# core_power.net
KiCad netlist of a schematic drawn in Altium Designer
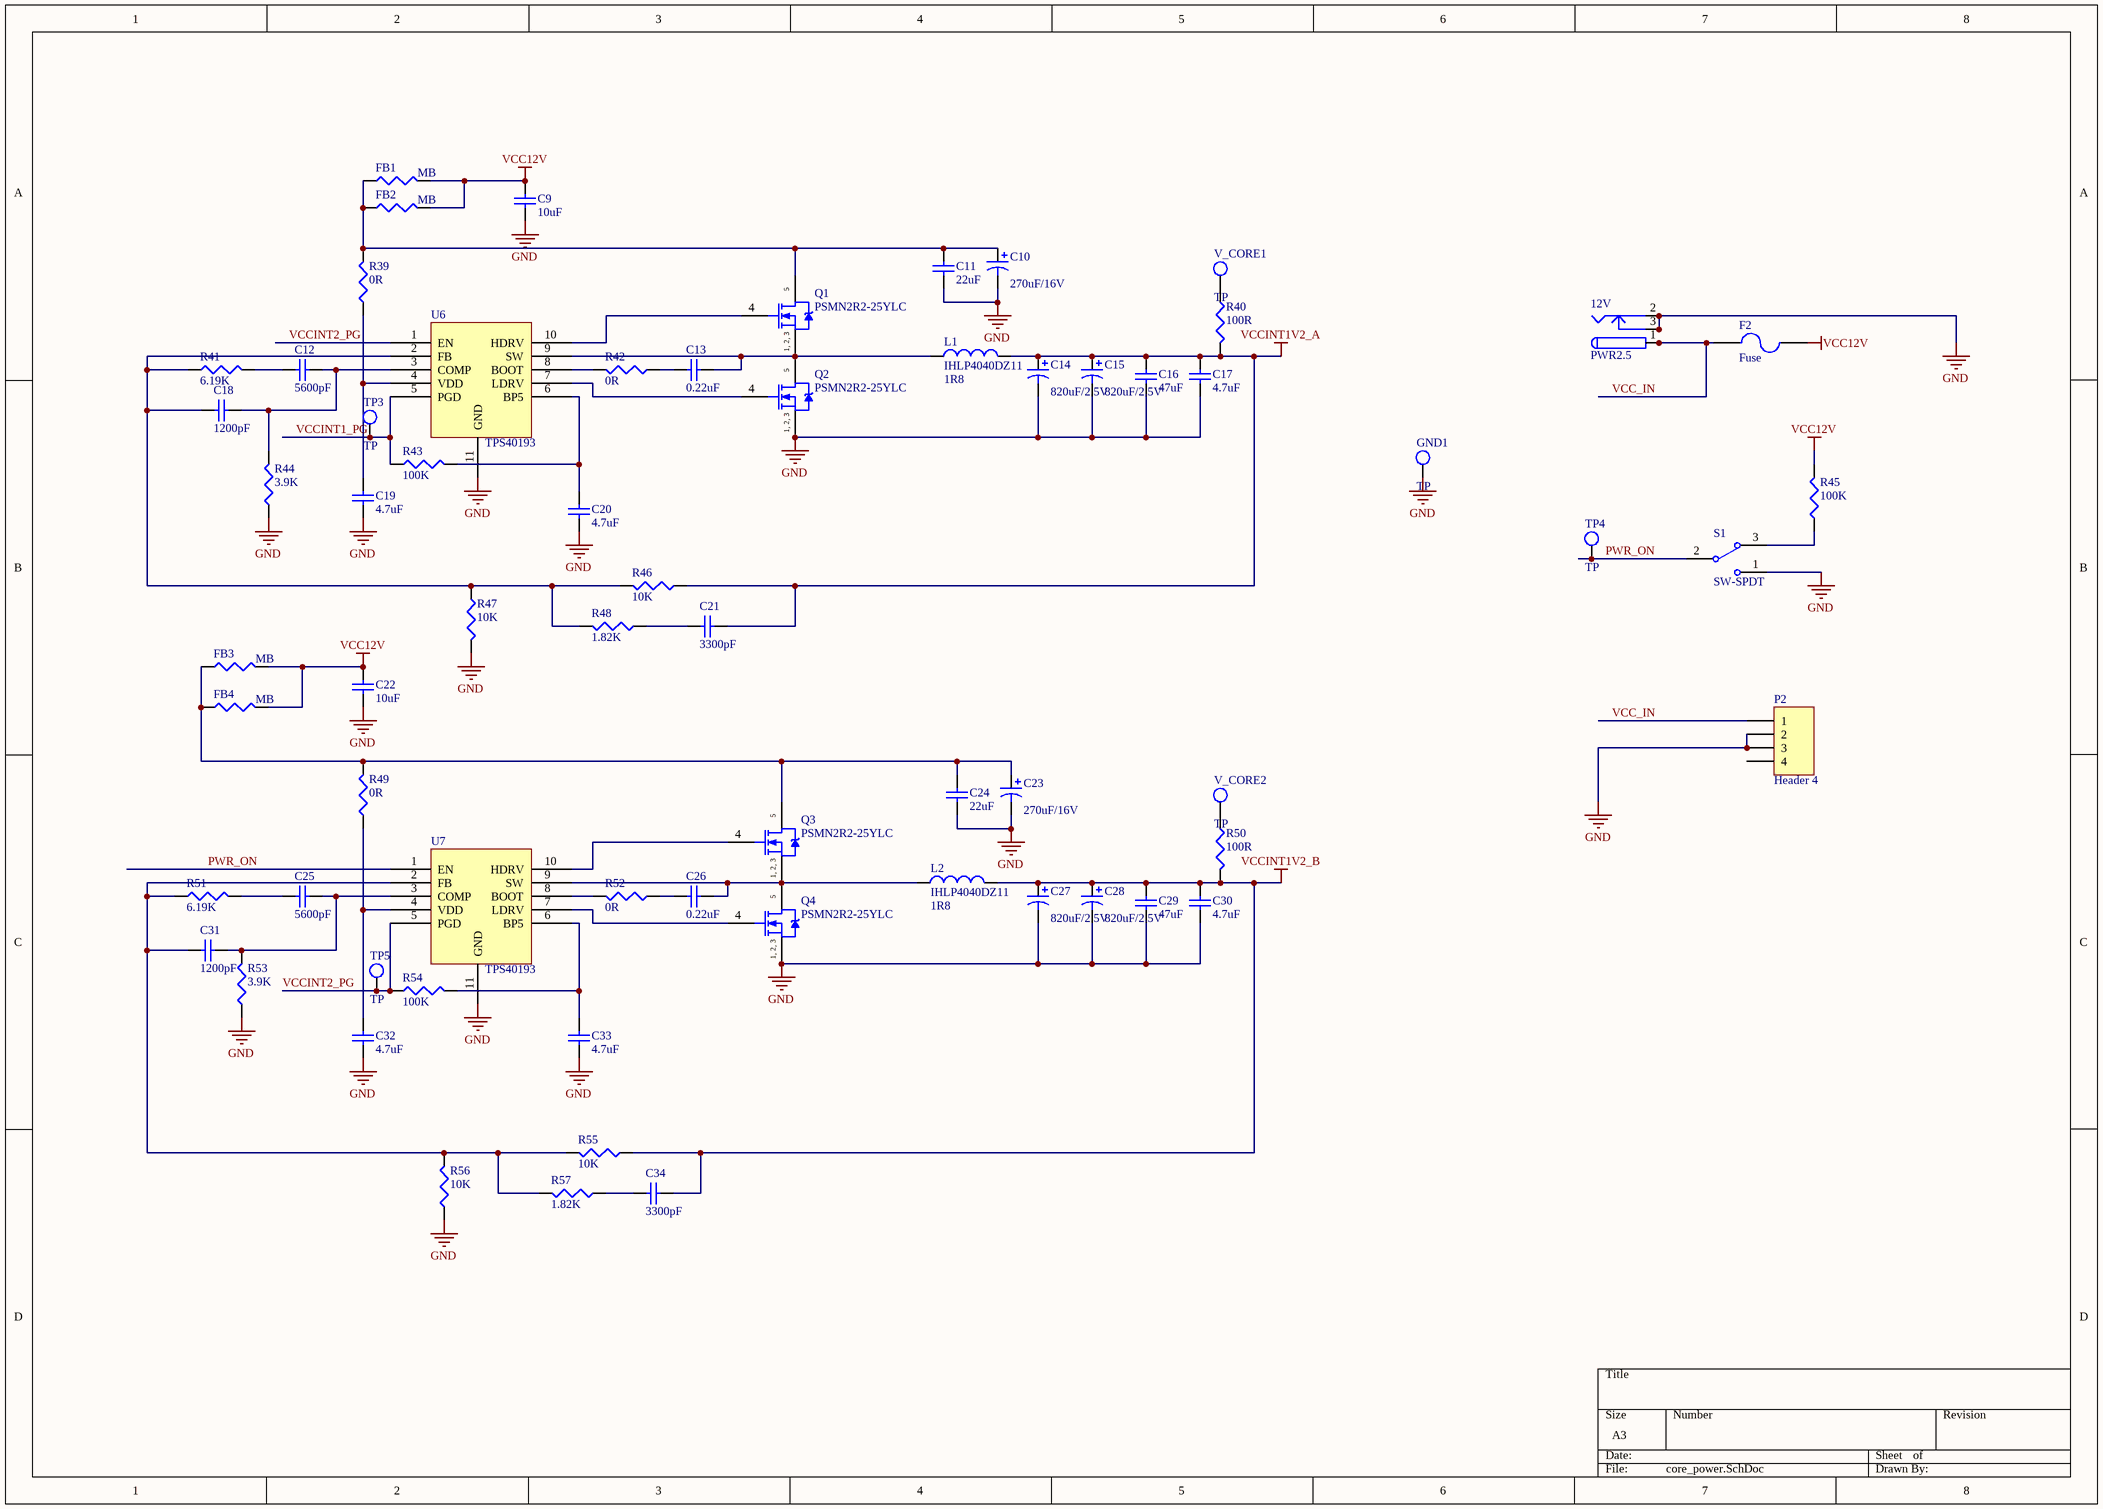
[diagram p0: core_power.SchDoc]

(export (version "E")
  (design (tool "Eeschema 10.0.6"))
  (components
    (comp (ref "12V")
      (value "PWR2.5")
      (footprint "KLD-0202")
      (description "Low Voltage Power Supply Connector")
      (fields (field (name "PUBLISHER") "Altium Limited"))
      (libsource (lib "Miscellaneous Connectors") (part "PWR2.5"))
    )
    (comp (ref "C9")
      (value "10uF")
      (footprint "CAPC3216N")
      (description "Capacitor (Semiconductor SIM Model)")
      (fields (field (name "PUBLISHER") "Altium Limited"))
      (libsource (lib "Miscellaneous Devices") (part "Cap Semi"))
    )
    (comp (ref "C10")
      (value "270uF/16V")
      (footprint "CAP8X8")
      (description "Polarized Capacitor (Radial)")
      (fields (field (name "PUBLISHER") "Altium Limited"))
      (libsource (lib "Miscellaneous Devices") (part "Cap Pol1"))
    )
    (comp (ref "C11")
      (value "22uF")
      (footprint "CAPC3225N")
      (description "Capacitor (Semiconductor SIM Model)")
      (fields (field (name "PUBLISHER") "Altium Limited"))
      (libsource (lib "Miscellaneous Devices") (part "Cap Semi"))
    )
    (comp (ref "C12")
      (value "5600pF")
      (footprint "CAPC1608N")
      (description "Capacitor (Semiconductor SIM Model)")
      (fields (field (name "PUBLISHER") "Altium Limited"))
      (libsource (lib "Miscellaneous Devices") (part "Cap Semi"))
    )
    (comp (ref "C13")
      (value "0.22uF")
      (footprint "CAPC1608N")
      (description "Capacitor (Semiconductor SIM Model)")
      (fields (field (name "PUBLISHER") "Altium Limited"))
      (libsource (lib "Miscellaneous Devices") (part "Cap Semi"))
    )
    (comp (ref "C14")
      (value "820uF/2.5V")
      (footprint "CAP8X8")
      (description "Polarized Capacitor (Radial)")
      (fields (field (name "PUBLISHER") "Altium Limited"))
      (libsource (lib "Miscellaneous Devices") (part "Cap Pol1"))
    )
    (comp (ref "C15")
      (value "820uF/2.5V")
      (footprint "CAP8X8")
      (description "Polarized Capacitor (Radial)")
      (fields (field (name "PUBLISHER") "Altium Limited"))
      (libsource (lib "Miscellaneous Devices") (part "Cap Pol1"))
    )
    (comp (ref "C16")
      (value "47uF")
      (footprint "CAPC3225N")
      (description "Capacitor (Semiconductor SIM Model)")
      (fields (field (name "PUBLISHER") "Altium Limited"))
      (libsource (lib "Miscellaneous Devices") (part "Cap Semi"))
    )
    (comp (ref "C17")
      (value "4.7uF")
      (footprint "CAPC1608N")
      (description "Capacitor (Semiconductor SIM Model)")
      (fields (field (name "PUBLISHER") "Altium Limited"))
      (libsource (lib "Miscellaneous Devices") (part "Cap Semi"))
    )
    (comp (ref "C18")
      (value "1200pF")
      (footprint "CAPC1608N")
      (description "Capacitor (Semiconductor SIM Model)")
      (fields (field (name "PUBLISHER") "Altium Limited"))
      (libsource (lib "Miscellaneous Devices") (part "Cap Semi"))
    )
    (comp (ref "C19")
      (value "4.7uF")
      (footprint "CAPC2012N")
      (description "Capacitor (Semiconductor SIM Model)")
      (fields (field (name "PUBLISHER") "Altium Limited"))
      (libsource (lib "Miscellaneous Devices") (part "Cap Semi"))
    )
    (comp (ref "C20")
      (value "4.7uF")
      (footprint "CAPC2012N")
      (description "Capacitor (Semiconductor SIM Model)")
      (fields (field (name "PUBLISHER") "Altium Limited"))
      (libsource (lib "Miscellaneous Devices") (part "Cap Semi"))
    )
    (comp (ref "C21")
      (value "3300pF")
      (footprint "CAPC1608N")
      (description "Capacitor (Semiconductor SIM Model)")
      (fields (field (name "PUBLISHER") "Altium Limited"))
      (libsource (lib "Miscellaneous Devices") (part "Cap Semi"))
    )
    (comp (ref "C22")
      (value "10uF")
      (footprint "CAPC3216N")
      (description "Capacitor (Semiconductor SIM Model)")
      (fields (field (name "PUBLISHER") "Altium Limited"))
      (libsource (lib "Miscellaneous Devices") (part "Cap Semi"))
    )
    (comp (ref "C23")
      (value "270uF/16V")
      (footprint "CAP8X8")
      (description "Polarized Capacitor (Radial)")
      (fields (field (name "PUBLISHER") "Altium Limited"))
      (libsource (lib "Miscellaneous Devices") (part "Cap Pol1"))
    )
    (comp (ref "C24")
      (value "22uF")
      (footprint "CAPC3225N")
      (description "Capacitor (Semiconductor SIM Model)")
      (fields (field (name "PUBLISHER") "Altium Limited"))
      (libsource (lib "Miscellaneous Devices") (part "Cap Semi"))
    )
    (comp (ref "C25")
      (value "5600pF")
      (footprint "CAPC1608N")
      (description "Capacitor (Semiconductor SIM Model)")
      (fields (field (name "PUBLISHER") "Altium Limited"))
      (libsource (lib "Miscellaneous Devices") (part "Cap Semi"))
    )
    (comp (ref "C26")
      (value "0.22uF")
      (footprint "CAPC1608N")
      (description "Capacitor (Semiconductor SIM Model)")
      (fields (field (name "PUBLISHER") "Altium Limited"))
      (libsource (lib "Miscellaneous Devices") (part "Cap Semi"))
    )
    (comp (ref "C27")
      (value "820uF/2.5V")
      (footprint "CAP8X8")
      (description "Polarized Capacitor (Radial)")
      (fields (field (name "PUBLISHER") "Altium Limited"))
      (libsource (lib "Miscellaneous Devices") (part "Cap Pol1"))
    )
    (comp (ref "C28")
      (value "820uF/2.5V")
      (footprint "CAP8X8")
      (description "Polarized Capacitor (Radial)")
      (fields (field (name "PUBLISHER") "Altium Limited"))
      (libsource (lib "Miscellaneous Devices") (part "Cap Pol1"))
    )
    (comp (ref "C29")
      (value "47uF")
      (footprint "CAPC3225N")
      (description "Capacitor (Semiconductor SIM Model)")
      (fields (field (name "PUBLISHER") "Altium Limited"))
      (libsource (lib "Miscellaneous Devices") (part "Cap Semi"))
    )
    (comp (ref "C30")
      (value "4.7uF")
      (footprint "CAPC1608N")
      (description "Capacitor (Semiconductor SIM Model)")
      (fields (field (name "PUBLISHER") "Altium Limited"))
      (libsource (lib "Miscellaneous Devices") (part "Cap Semi"))
    )
    (comp (ref "C31")
      (value "1200pF")
      (footprint "CAPC1608N")
      (description "Capacitor (Semiconductor SIM Model)")
      (fields (field (name "PUBLISHER") "Altium Limited"))
      (libsource (lib "Miscellaneous Devices") (part "Cap Semi"))
    )
    (comp (ref "C32")
      (value "4.7uF")
      (footprint "CAPC2012N")
      (description "Capacitor (Semiconductor SIM Model)")
      (fields (field (name "PUBLISHER") "Altium Limited"))
      (libsource (lib "Miscellaneous Devices") (part "Cap Semi"))
    )
    (comp (ref "C33")
      (value "4.7uF")
      (footprint "CAPC2012N")
      (description "Capacitor (Semiconductor SIM Model)")
      (fields (field (name "PUBLISHER") "Altium Limited"))
      (libsource (lib "Miscellaneous Devices") (part "Cap Semi"))
    )
    (comp (ref "C34")
      (value "3300pF")
      (footprint "CAPC1608N")
      (description "Capacitor (Semiconductor SIM Model)")
      (fields (field (name "PUBLISHER") "Altium Limited"))
      (libsource (lib "Miscellaneous Devices") (part "Cap Semi"))
    )
    (comp (ref "F2")
      (value "Fuse")
      (footprint "RESC5025N")
      (fields (field (name "PUBLISHER") "Altium Limited"))
      (libsource (lib "Miscellaneous Devices") (part "Fuse 2"))
    )
    (comp (ref "FB1")
      (value "MB")
      (footprint "INDC3216N")
      (description "Resistor")
      (fields (field (name "PUBLISHER") "Altium Limited"))
      (libsource (lib "Miscellaneous Devices") (part "Res3"))
    )
    (comp (ref "FB2")
      (value "MB")
      (footprint "INDC3216N")
      (description "Resistor")
      (fields (field (name "PUBLISHER") "Altium Limited"))
      (libsource (lib "Miscellaneous Devices") (part "Res3"))
    )
    (comp (ref "FB3")
      (value "MB")
      (footprint "INDC3216N")
      (description "Resistor")
      (fields (field (name "PUBLISHER") "Altium Limited"))
      (libsource (lib "Miscellaneous Devices") (part "Res3"))
    )
    (comp (ref "FB4")
      (value "MB")
      (footprint "INDC3216N")
      (description "Resistor")
      (fields (field (name "PUBLISHER") "Altium Limited"))
      (libsource (lib "Miscellaneous Devices") (part "Res3"))
    )
    (comp (ref "GND1") (value "TP") (footprint "PIN1") (libsource (lib "S6") (part "TP")))
    (comp (ref "L1")
      (value "IHLP4040DZ11")
      (footprint "IHLP4040")
      (description "Inductor")
      (fields (field (name "ALTIUM_VALUE") "1R8") (field (name "PUBLISHER") "Altium Limited"))
      (libsource (lib "Miscellaneous Devices") (part "Inductor"))
    )
    (comp (ref "L2")
      (value "IHLP4040DZ11")
      (footprint "IHLP4040")
      (description "Inductor")
      (fields (field (name "ALTIUM_VALUE") "1R8") (field (name "PUBLISHER") "Altium Limited"))
      (libsource (lib "Miscellaneous Devices") (part "Inductor"))
    )
    (comp (ref "P2")
      (value "Header 4")
      (footprint "S61:015244441")
      (description "Header, 4-Pin")
      (fields (field (name "PUBLISHER") "Altium Limited"))
      (libsource (lib "Miscellaneous Connectors") (part "Header 4"))
    )
    (comp (ref "Q1") (value "PSMN2R2-25YLC") (footprint "LFPAK") (libsource (lib "S6") (part "HAT216X")))
    (comp (ref "Q2") (value "PSMN2R2-25YLC") (footprint "LFPAK") (libsource (lib "S6") (part "HAT216X")))
    (comp (ref "Q3") (value "PSMN2R2-25YLC") (footprint "LFPAK") (libsource (lib "S6") (part "HAT216X")))
    (comp (ref "Q4") (value "PSMN2R2-25YLC") (footprint "LFPAK") (libsource (lib "S6") (part "HAT216X")))
    (comp (ref "R39")
      (value "0R")
      (footprint "RESC1608N")
      (description "Resistor")
      (fields (field (name "PUBLISHER") "Altium Limited"))
      (libsource (lib "Miscellaneous Devices") (part "Res3"))
    )
    (comp (ref "R40")
      (value "100R")
      (footprint "RESC1005N")
      (description "Resistor")
      (fields (field (name "PUBLISHER") "Altium Limited"))
      (libsource (lib "Miscellaneous Devices") (part "Res3"))
    )
    (comp (ref "R41")
      (value "6.19K")
      (footprint "RESC1608N")
      (description "Resistor")
      (fields (field (name "PUBLISHER") "Altium Limited"))
      (libsource (lib "Miscellaneous Devices") (part "Res3"))
    )
    (comp (ref "R42")
      (value "0R")
      (footprint "RESC1608N")
      (description "Resistor")
      (fields (field (name "PUBLISHER") "Altium Limited"))
      (libsource (lib "Miscellaneous Devices") (part "Res3"))
    )
    (comp (ref "R43")
      (value "100K")
      (footprint "RESC1005N")
      (description "Resistor")
      (fields (field (name "PUBLISHER") "Altium Limited"))
      (libsource (lib "Miscellaneous Devices") (part "Res3"))
    )
    (comp (ref "R44")
      (value "3.9K")
      (footprint "RESC1608N")
      (description "Resistor")
      (fields (field (name "PUBLISHER") "Altium Limited"))
      (libsource (lib "Miscellaneous Devices") (part "Res3"))
    )
    (comp (ref "R45")
      (value "100K")
      (footprint "RESC1005N")
      (description "Resistor")
      (fields (field (name "PUBLISHER") "Altium Limited"))
      (libsource (lib "Miscellaneous Devices") (part "Res3"))
    )
    (comp (ref "R46")
      (value "10K")
      (footprint "RESC1608N")
      (description "Resistor")
      (fields (field (name "PUBLISHER") "Altium Limited"))
      (libsource (lib "Miscellaneous Devices") (part "Res3"))
    )
    (comp (ref "R47")
      (value "10K")
      (footprint "RESC1608N")
      (description "Resistor")
      (fields (field (name "PUBLISHER") "Altium Limited"))
      (libsource (lib "Miscellaneous Devices") (part "Res3"))
    )
    (comp (ref "R48")
      (value "1.82K")
      (footprint "RESC1608N")
      (description "Resistor")
      (fields (field (name "PUBLISHER") "Altium Limited"))
      (libsource (lib "Miscellaneous Devices") (part "Res3"))
    )
    (comp (ref "R49")
      (value "0R")
      (footprint "RESC1608N")
      (description "Resistor")
      (fields (field (name "PUBLISHER") "Altium Limited"))
      (libsource (lib "Miscellaneous Devices") (part "Res3"))
    )
    (comp (ref "R50")
      (value "100R")
      (footprint "RESC1005N")
      (description "Resistor")
      (fields (field (name "PUBLISHER") "Altium Limited"))
      (libsource (lib "Miscellaneous Devices") (part "Res3"))
    )
    (comp (ref "R51")
      (value "6.19K")
      (footprint "RESC1608N")
      (description "Resistor")
      (fields (field (name "PUBLISHER") "Altium Limited"))
      (libsource (lib "Miscellaneous Devices") (part "Res3"))
    )
    (comp (ref "R52")
      (value "0R")
      (footprint "RESC1608N")
      (description "Resistor")
      (fields (field (name "PUBLISHER") "Altium Limited"))
      (libsource (lib "Miscellaneous Devices") (part "Res3"))
    )
    (comp (ref "R53")
      (value "3.9K")
      (footprint "RESC1608N")
      (description "Resistor")
      (fields (field (name "PUBLISHER") "Altium Limited"))
      (libsource (lib "Miscellaneous Devices") (part "Res3"))
    )
    (comp (ref "R54")
      (value "100K")
      (footprint "RESC1005N")
      (description "Resistor")
      (fields (field (name "PUBLISHER") "Altium Limited"))
      (libsource (lib "Miscellaneous Devices") (part "Res3"))
    )
    (comp (ref "R55")
      (value "10K")
      (footprint "RESC1608N")
      (description "Resistor")
      (fields (field (name "PUBLISHER") "Altium Limited"))
      (libsource (lib "Miscellaneous Devices") (part "Res3"))
    )
    (comp (ref "R56")
      (value "10K")
      (footprint "RESC1608N")
      (description "Resistor")
      (fields (field (name "PUBLISHER") "Altium Limited"))
      (libsource (lib "Miscellaneous Devices") (part "Res3"))
    )
    (comp (ref "R57")
      (value "1.82K")
      (footprint "RESC1608N")
      (description "Resistor")
      (fields (field (name "PUBLISHER") "Altium Limited"))
      (libsource (lib "Miscellaneous Devices") (part "Res3"))
    )
    (comp (ref "S1")
      (value "SW-SPDT")
      (footprint "SW3_S")
      (description "SPDT Subminiature Toggle Switch, Right Angle Mounting, Vertical Actuation")
      (fields (field (name "PUBLISHER") "Altium Limited"))
      (libsource (lib "Miscellaneous Devices") (part "SW-SPDT"))
    )
    (comp (ref "TP3") (value "TP") (footprint "TP") (libsource (lib "S6") (part "TP")))
    (comp (ref "TP4") (value "TP") (footprint "TP") (libsource (lib "S6") (part "TP")))
    (comp (ref "TP5") (value "TP") (footprint "TP") (libsource (lib "S6") (part "TP")))
    (comp (ref "U6") (value "TPS40193") (footprint "SON10") (libsource (lib "S6") (part "TPS40193")))
    (comp (ref "U7") (value "TPS40193") (footprint "SON10") (libsource (lib "S6") (part "TPS40193")))
    (comp (ref "V_CORE1") (value "TP") (footprint "PIN1") (libsource (lib "S6") (part "TP")))
    (comp (ref "V_CORE2") (value "TP") (footprint "PIN1") (libsource (lib "S6") (part "TP")))
  )
  (nets
    (net (code "1") (name "/PWR_ON") (class "Default")
      (node (ref "S1") (pin "2") (pinfunction "2_2") (pintype "passive"))
      (node (ref "TP4") (pin "1") (pinfunction "TP_1") (pintype "passive"))
      (node (ref "U7") (pin "1") (pinfunction "EN_1") (pintype "passive"))
    )
    (net (code "2") (name "/VCCINT1_PG") (class "Default")
      (node (ref "R43") (pin "1") (pinfunction "1_1") (pintype "passive"))
      (node (ref "TP3") (pin "1") (pinfunction "TP_1") (pintype "passive"))
      (node (ref "U6") (pin "5") (pinfunction "PGD_5") (pintype "passive"))
    )
    (net (code "3") (name "/VCCINT2_PG") (class "Default")
      (node (ref "R54") (pin "1") (pinfunction "1_1") (pintype "passive"))
      (node (ref "TP5") (pin "1") (pinfunction "TP_1") (pintype "passive"))
      (node (ref "U6") (pin "1") (pinfunction "EN_1") (pintype "passive"))
      (node (ref "U7") (pin "5") (pinfunction "PGD_5") (pintype "passive"))
    )
    (net (code "4") (name "/VCC_IN") (class "Default")
      (node (ref "12V") (pin "1") (pinfunction "1_1") (pintype "power_in"))
      (node (ref "12V") (pin "1A") (pinfunction "1A_1A") (pintype "power_in"))
      (node (ref "12V") (pin "1B") (pinfunction "1B_1B") (pintype "power_in"))
      (node (ref "F2") (pin "1") (pinfunction "1_1") (pintype "passive"))
      (node (ref "P2") (pin "1") (pinfunction "1_1") (pintype "passive"))
    )
    (net (code "5") (name "GND") (class "Default")
      (node (ref "12V") (pin "2") (pinfunction "2_2") (pintype "power_in"))
      (node (ref "12V") (pin "2A") (pinfunction "2A_2A") (pintype "power_in"))
      (node (ref "12V") (pin "2B") (pinfunction "2B_2B") (pintype "power_in"))
      (node (ref "12V") (pin "3") (pinfunction "3_3") (pintype "power_in"))
      (node (ref "12V") (pin "3A") (pinfunction "3A_3A") (pintype "power_in"))
      (node (ref "12V") (pin "3B") (pinfunction "3B_3B") (pintype "power_in"))
      (node (ref "C10") (pin "2") (pinfunction "2_2") (pintype "passive"))
      (node (ref "C11") (pin "1") (pinfunction "1_1") (pintype "passive"))
      (node (ref "C14") (pin "2") (pinfunction "2_2") (pintype "passive"))
      (node (ref "C15") (pin "2") (pinfunction "2_2") (pintype "passive"))
      (node (ref "C16") (pin "1") (pinfunction "1_1") (pintype "passive"))
      (node (ref "C17") (pin "1") (pinfunction "1_1") (pintype "passive"))
      (node (ref "C19") (pin "2") (pinfunction "2_2") (pintype "passive"))
      (node (ref "C20") (pin "1") (pinfunction "1_1") (pintype "passive"))
      (node (ref "C22") (pin "1") (pinfunction "1_1") (pintype "passive"))
      (node (ref "C23") (pin "2") (pinfunction "2_2") (pintype "passive"))
      (node (ref "C24") (pin "1") (pinfunction "1_1") (pintype "passive"))
      (node (ref "C27") (pin "2") (pinfunction "2_2") (pintype "passive"))
      (node (ref "C28") (pin "2") (pinfunction "2_2") (pintype "passive"))
      (node (ref "C29") (pin "1") (pinfunction "1_1") (pintype "passive"))
      (node (ref "C30") (pin "1") (pinfunction "1_1") (pintype "passive"))
      (node (ref "C32") (pin "1") (pinfunction "1_1") (pintype "passive"))
      (node (ref "C33") (pin "2") (pinfunction "2_2") (pintype "passive"))
      (node (ref "C9") (pin "1") (pinfunction "1_1") (pintype "passive"))
      (node (ref "GND1") (pin "1") (pinfunction "TP_1") (pintype "passive"))
      (node (ref "P2") (pin "2") (pinfunction "2_2") (pintype "passive"))
      (node (ref "P2") (pin "3") (pinfunction "3_3") (pintype "passive"))
      (node (ref "Q2") (pin "1") (pinfunction "S_1") (pintype "passive"))
      (node (ref "Q2") (pin "2") (pinfunction "S_2") (pintype "passive"))
      (node (ref "Q2") (pin "3") (pinfunction "S_3") (pintype "passive"))
      (node (ref "Q4") (pin "1") (pinfunction "S_1") (pintype "passive"))
      (node (ref "Q4") (pin "2") (pinfunction "S_2") (pintype "passive"))
      (node (ref "Q4") (pin "3") (pinfunction "S_3") (pintype "passive"))
      (node (ref "R44") (pin "1") (pinfunction "1_1") (pintype "passive"))
      (node (ref "R47") (pin "2") (pinfunction "2_2") (pintype "passive"))
      (node (ref "R53") (pin "1") (pinfunction "1_1") (pintype "passive"))
      (node (ref "R56") (pin "1") (pinfunction "1_1") (pintype "passive"))
      (node (ref "S1") (pin "1") (pinfunction "1_1") (pintype "passive"))
      (node (ref "U6") (pin "11") (pinfunction "GND_11") (pintype "passive"))
      (node (ref "U7") (pin "11") (pinfunction "GND_11") (pintype "passive"))
    )
    (net (code "6") (name "Net-(C12-Pad2)") (class "Default")
      (node (ref "C12") (pin "2") (pinfunction "2_2") (pintype "passive"))
      (node (ref "R41") (pin "2") (pinfunction "2_2") (pintype "passive"))
    )
    (net (code "7") (name "Net-(C13-Pad2)") (class "Default")
      (node (ref "C13") (pin "2") (pinfunction "2_2") (pintype "passive"))
      (node (ref "R42") (pin "1") (pinfunction "1_1") (pintype "passive"))
    )
    (net (code "8") (name "Net-(C21-Pad1)") (class "Default")
      (node (ref "C21") (pin "1") (pinfunction "1_1") (pintype "passive"))
      (node (ref "R48") (pin "1") (pinfunction "1_1") (pintype "passive"))
    )
    (net (code "9") (name "Net-(C25-Pad2)") (class "Default")
      (node (ref "C25") (pin "2") (pinfunction "2_2") (pintype "passive"))
      (node (ref "R51") (pin "2") (pinfunction "2_2") (pintype "passive"))
    )
    (net (code "10") (name "Net-(C26-Pad2)") (class "Default")
      (node (ref "C26") (pin "2") (pinfunction "2_2") (pintype "passive"))
      (node (ref "R52") (pin "1") (pinfunction "1_1") (pintype "passive"))
    )
    (net (code "11") (name "Net-(C34-Pad1)") (class "Default")
      (node (ref "C34") (pin "1") (pinfunction "1_1") (pintype "passive"))
      (node (ref "R57") (pin "1") (pinfunction "1_1") (pintype "passive"))
    )
    (net (code "12") (name "Net-(Q1-D)") (class "Default")
      (node (ref "C10") (pin "1") (pinfunction "1_1") (pintype "passive"))
      (node (ref "C11") (pin "2") (pinfunction "2_2") (pintype "passive"))
      (node (ref "FB1") (pin "1") (pinfunction "1_1") (pintype "passive"))
      (node (ref "FB2") (pin "1") (pinfunction "1_1") (pintype "passive"))
      (node (ref "Q1") (pin "5") (pinfunction "D_5") (pintype "passive"))
      (node (ref "R39") (pin "2") (pinfunction "2_2") (pintype "passive"))
    )
    (net (code "13") (name "Net-(Q1-G)") (class "Default")
      (node (ref "Q1") (pin "4") (pinfunction "G_4") (pintype "passive"))
      (node (ref "U6") (pin "10") (pinfunction "HDRV_10") (pintype "passive"))
    )
    (net (code "14") (name "Net-(Q2-D)") (class "Default")
      (node (ref "C13") (pin "1") (pinfunction "1_1") (pintype "passive"))
      (node (ref "L1") (pin "1") (pinfunction "1_1") (pintype "passive"))
      (node (ref "Q1") (pin "1") (pinfunction "S_1") (pintype "passive"))
      (node (ref "Q1") (pin "2") (pinfunction "S_2") (pintype "passive"))
      (node (ref "Q1") (pin "3") (pinfunction "S_3") (pintype "passive"))
      (node (ref "Q2") (pin "5") (pinfunction "D_5") (pintype "passive"))
      (node (ref "U6") (pin "9") (pinfunction "SW_9") (pintype "passive"))
    )
    (net (code "15") (name "Net-(Q2-G)") (class "Default")
      (node (ref "Q2") (pin "4") (pinfunction "G_4") (pintype "passive"))
      (node (ref "U6") (pin "7") (pinfunction "LDRV_7") (pintype "passive"))
    )
    (net (code "16") (name "Net-(Q3-D)") (class "Default")
      (node (ref "C23") (pin "1") (pinfunction "1_1") (pintype "passive"))
      (node (ref "C24") (pin "2") (pinfunction "2_2") (pintype "passive"))
      (node (ref "FB3") (pin "1") (pinfunction "1_1") (pintype "passive"))
      (node (ref "FB4") (pin "1") (pinfunction "1_1") (pintype "passive"))
      (node (ref "Q3") (pin "5") (pinfunction "D_5") (pintype "passive"))
      (node (ref "R49") (pin "2") (pinfunction "2_2") (pintype "passive"))
    )
    (net (code "17") (name "Net-(Q3-G)") (class "Default")
      (node (ref "Q3") (pin "4") (pinfunction "G_4") (pintype "passive"))
      (node (ref "U7") (pin "10") (pinfunction "HDRV_10") (pintype "passive"))
    )
    (net (code "18") (name "Net-(Q4-D)") (class "Default")
      (node (ref "C26") (pin "1") (pinfunction "1_1") (pintype "passive"))
      (node (ref "L2") (pin "1") (pinfunction "1_1") (pintype "passive"))
      (node (ref "Q3") (pin "1") (pinfunction "S_1") (pintype "passive"))
      (node (ref "Q3") (pin "2") (pinfunction "S_2") (pintype "passive"))
      (node (ref "Q3") (pin "3") (pinfunction "S_3") (pintype "passive"))
      (node (ref "Q4") (pin "5") (pinfunction "D_5") (pintype "passive"))
      (node (ref "U7") (pin "9") (pinfunction "SW_9") (pintype "passive"))
    )
    (net (code "19") (name "Net-(Q4-G)") (class "Default")
      (node (ref "Q4") (pin "4") (pinfunction "G_4") (pintype "passive"))
      (node (ref "U7") (pin "7") (pinfunction "LDRV_7") (pintype "passive"))
    )
    (net (code "20") (name "Net-(R45-Pad1)") (class "Default")
      (node (ref "R45") (pin "1") (pinfunction "1_1") (pintype "passive"))
      (node (ref "S1") (pin "3") (pinfunction "3_3") (pintype "passive"))
    )
    (net (code "21") (name "Net-(U6-BOOT)") (class "Default")
      (node (ref "R42") (pin "2") (pinfunction "2_2") (pintype "passive"))
      (node (ref "U6") (pin "8") (pinfunction "BOOT_8") (pintype "passive"))
    )
    (net (code "22") (name "Net-(U6-BP5)") (class "Default")
      (node (ref "C20") (pin "2") (pinfunction "2_2") (pintype "passive"))
      (node (ref "R43") (pin "2") (pinfunction "2_2") (pintype "passive"))
      (node (ref "U6") (pin "6") (pinfunction "BP5_6") (pintype "passive"))
    )
    (net (code "23") (name "Net-(U6-COMP)") (class "Default")
      (node (ref "C12") (pin "1") (pinfunction "1_1") (pintype "passive"))
      (node (ref "C18") (pin "1") (pinfunction "1_1") (pintype "passive"))
      (node (ref "R44") (pin "2") (pinfunction "2_2") (pintype "passive"))
      (node (ref "U6") (pin "3") (pinfunction "COMP_3") (pintype "passive"))
    )
    (net (code "24") (name "Net-(U6-FB)") (class "Default")
      (node (ref "C18") (pin "2") (pinfunction "2_2") (pintype "passive"))
      (node (ref "R41") (pin "1") (pinfunction "1_1") (pintype "passive"))
      (node (ref "R46") (pin "2") (pinfunction "2_2") (pintype "passive"))
      (node (ref "R47") (pin "1") (pinfunction "1_1") (pintype "passive"))
      (node (ref "R48") (pin "2") (pinfunction "2_2") (pintype "passive"))
      (node (ref "U6") (pin "2") (pinfunction "FB_2") (pintype "passive"))
    )
    (net (code "25") (name "Net-(U6-VDD)") (class "Default")
      (node (ref "C19") (pin "1") (pinfunction "1_1") (pintype "passive"))
      (node (ref "R39") (pin "1") (pinfunction "1_1") (pintype "passive"))
      (node (ref "U6") (pin "4") (pinfunction "VDD_4") (pintype "passive"))
    )
    (net (code "26") (name "Net-(U7-BOOT)") (class "Default")
      (node (ref "R52") (pin "2") (pinfunction "2_2") (pintype "passive"))
      (node (ref "U7") (pin "8") (pinfunction "BOOT_8") (pintype "passive"))
    )
    (net (code "27") (name "Net-(U7-BP5)") (class "Default")
      (node (ref "C33") (pin "1") (pinfunction "1_1") (pintype "passive"))
      (node (ref "R54") (pin "2") (pinfunction "2_2") (pintype "passive"))
      (node (ref "U7") (pin "6") (pinfunction "BP5_6") (pintype "passive"))
    )
    (net (code "28") (name "Net-(U7-COMP)") (class "Default")
      (node (ref "C25") (pin "1") (pinfunction "1_1") (pintype "passive"))
      (node (ref "C31") (pin "1") (pinfunction "1_1") (pintype "passive"))
      (node (ref "R53") (pin "2") (pinfunction "2_2") (pintype "passive"))
      (node (ref "U7") (pin "3") (pinfunction "COMP_3") (pintype "passive"))
    )
    (net (code "29") (name "Net-(U7-FB)") (class "Default")
      (node (ref "C31") (pin "2") (pinfunction "2_2") (pintype "passive"))
      (node (ref "R51") (pin "1") (pinfunction "1_1") (pintype "passive"))
      (node (ref "R55") (pin "2") (pinfunction "2_2") (pintype "passive"))
      (node (ref "R56") (pin "2") (pinfunction "2_2") (pintype "passive"))
      (node (ref "R57") (pin "2") (pinfunction "2_2") (pintype "passive"))
      (node (ref "U7") (pin "2") (pinfunction "FB_2") (pintype "passive"))
    )
    (net (code "30") (name "Net-(U7-VDD)") (class "Default")
      (node (ref "C32") (pin "2") (pinfunction "2_2") (pintype "passive"))
      (node (ref "R49") (pin "1") (pinfunction "1_1") (pintype "passive"))
      (node (ref "U7") (pin "4") (pinfunction "VDD_4") (pintype "passive"))
    )
    (net (code "31") (name "Net-(V_CORE1-TP)") (class "Default")
      (node (ref "R40") (pin "1") (pinfunction "1_1") (pintype "passive"))
      (node (ref "V_CORE1") (pin "1") (pinfunction "TP_1") (pintype "passive"))
    )
    (net (code "32") (name "Net-(V_CORE2-TP)") (class "Default")
      (node (ref "R50") (pin "1") (pinfunction "1_1") (pintype "passive"))
      (node (ref "V_CORE2") (pin "1") (pinfunction "TP_1") (pintype "passive"))
    )
    (net (code "33") (name "VCC12V") (class "Default")
      (node (ref "C22") (pin "2") (pinfunction "2_2") (pintype "passive"))
      (node (ref "C9") (pin "2") (pinfunction "2_2") (pintype "passive"))
      (node (ref "F2") (pin "2") (pinfunction "2_2") (pintype "passive"))
      (node (ref "FB1") (pin "2") (pinfunction "2_2") (pintype "passive"))
      (node (ref "FB2") (pin "2") (pinfunction "2_2") (pintype "passive"))
      (node (ref "FB3") (pin "2") (pinfunction "2_2") (pintype "passive"))
      (node (ref "FB4") (pin "2") (pinfunction "2_2") (pintype "passive"))
      (node (ref "R45") (pin "2") (pinfunction "2_2") (pintype "passive"))
    )
    (net (code "34") (name "VCCINT1V2_A") (class "Default")
      (node (ref "C14") (pin "1") (pinfunction "1_1") (pintype "passive"))
      (node (ref "C15") (pin "1") (pinfunction "1_1") (pintype "passive"))
      (node (ref "C16") (pin "2") (pinfunction "2_2") (pintype "passive"))
      (node (ref "C17") (pin "2") (pinfunction "2_2") (pintype "passive"))
      (node (ref "C21") (pin "2") (pinfunction "2_2") (pintype "passive"))
      (node (ref "L1") (pin "2") (pinfunction "2_2") (pintype "passive"))
      (node (ref "R40") (pin "2") (pinfunction "2_2") (pintype "passive"))
      (node (ref "R46") (pin "1") (pinfunction "1_1") (pintype "passive"))
    )
    (net (code "35") (name "VCCINT1V2_B") (class "Default")
      (node (ref "C27") (pin "1") (pinfunction "1_1") (pintype "passive"))
      (node (ref "C28") (pin "1") (pinfunction "1_1") (pintype "passive"))
      (node (ref "C29") (pin "2") (pinfunction "2_2") (pintype "passive"))
      (node (ref "C30") (pin "2") (pinfunction "2_2") (pintype "passive"))
      (node (ref "C34") (pin "2") (pinfunction "2_2") (pintype "passive"))
      (node (ref "L2") (pin "2") (pinfunction "2_2") (pintype "passive"))
      (node (ref "R50") (pin "2") (pinfunction "2_2") (pintype "passive"))
      (node (ref "R55") (pin "1") (pinfunction "1_1") (pintype "passive"))
    )
    (net (code "36") (name "unconnected-(P2-Pad4)") (class "Default")
      (node (ref "P2") (pin "4") (pinfunction "4_4") (pintype "passive"))
    )
  )
)
